# SHDN-CURRENT-S08-V00-5kWDetection.net
KiCad netlist of a schematic drawn in Altium Designer
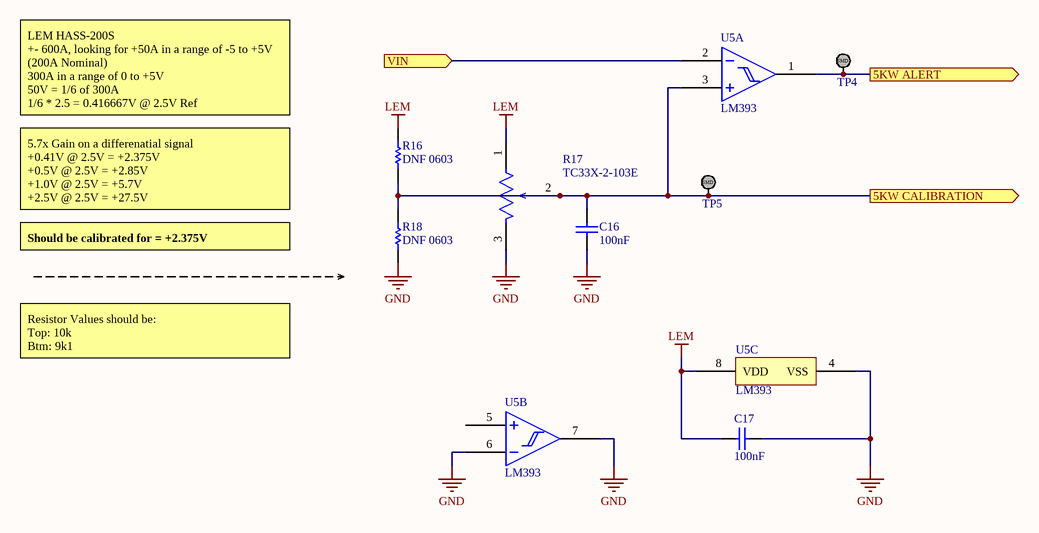
[diagram p0: SHDN-CURRENT-S08-V00-5kWDetection.SchDoc]

(export (version "E")
  (design (tool "Eeschema 10.0.6"))
  (components
    (comp (ref "C16")
      (value "100nF")
      (footprint "Cap_Ceramic_0603")
      (description "Capacitor, Ceramic, SMD, 100nF, 50V, 5%, X7R, 0603")
      (libsource (lib "StandardCapacitors") (part "100nF 50V 5% X7R 0603"))
    )
    (comp (ref "C17")
      (value "100nF")
      (footprint "Cap_Ceramic_0603")
      (description "Capacitor, Ceramic, SMD, 100nF, 50V, 5%, X7R, 0603")
      (libsource (lib "StandardCapacitors") (part "100nF 50V 5% X7R 0603"))
    )
    (comp (ref "R16")
      (value "DNF 0603")
      (footprint "Res_ThinFilm_0603")
      (description "Resistor, SMD, DNF, 0.1W, 0603")
      (libsource (lib "StandardResistors") (part "DNF 0603"))
    )
    (comp (ref "R17")
      (value "TC33X-2-103E")
      (footprint "TC33")
      (description "10 kOhms 0.1W, 1/10W J Lead Surface Mount Trimmer Potentiometer Cermet 1 Turn Top Adjustment")
      (libsource (lib "QUTMS_TrimmerLibrary") (part "TC33X-2-103E"))
    )
    (comp (ref "R18")
      (value "DNF 0603")
      (footprint "Res_ThinFilm_0603")
      (description "Resistor, SMD, DNF, 0.1W, 0603")
      (libsource (lib "StandardResistors") (part "DNF 0603"))
    )
    (comp (ref "TP4")
      (value "TestPoint_SMD")
      (footprint "TestPointSMD")
      (libsource (lib "StandardTest") (part "TestPoint_SMD"))
    )
    (comp (ref "TP5")
      (value "TestPoint_SMD")
      (footprint "TestPointSMD")
      (libsource (lib "StandardTest") (part "TestPoint_SMD"))
    )
    (comp (ref "U5")
      (value "LM393")
      (footprint "TSSOP-8")
      (description "General Purpose Comparitor 2 Circuit 8-SOIC")
      (libsource (lib "") (part "LM393_1"))
    )
  )
  (nets
    (net (code "1") (name "/5KW ALERT") (class "Default")
      (node (ref "TP4") (pin "1") (pinfunction "1_1") (pintype "passive"))
      (node (ref "U5") (pin "1") (pinfunction "OUT1_1") (pintype "passive"))
    )
    (net (code "2") (name "/5KW CALIBRATION") (class "Default")
      (node (ref "C16") (pin "2") (pinfunction "2_2") (pintype "passive"))
      (node (ref "R16") (pin "1") (pinfunction "1_1") (pintype "passive"))
      (node (ref "R17") (pin "2") (pinfunction "2_2") (pintype "passive"))
      (node (ref "R18") (pin "2") (pinfunction "2_2") (pintype "passive"))
      (node (ref "TP5") (pin "1") (pinfunction "1_1") (pintype "passive"))
      (node (ref "U5") (pin "3") (pinfunction "IN1+_3") (pintype "passive"))
    )
    (net (code "3") (name "/VIN") (class "Default")
      (node (ref "U5") (pin "2") (pinfunction "IN1-_2") (pintype "passive"))
    )
    (net (code "4") (name "GND") (class "Default")
      (node (ref "C16") (pin "1") (pinfunction "1_1") (pintype "passive"))
      (node (ref "C17") (pin "2") (pinfunction "2_2") (pintype "passive"))
      (node (ref "R17") (pin "3") (pinfunction "3_3") (pintype "passive"))
      (node (ref "R18") (pin "1") (pinfunction "1_1") (pintype "passive"))
      (node (ref "U5") (pin "4") (pinfunction "VSS_4") (pintype "passive"))
      (node (ref "U5") (pin "6") (pinfunction "IN2-_6") (pintype "passive"))
      (node (ref "U5") (pin "7") (pinfunction "OUT1_7") (pintype "passive"))
    )
    (net (code "5") (name "LEM") (class "Default")
      (node (ref "C17") (pin "1") (pinfunction "1_1") (pintype "passive"))
      (node (ref "R16") (pin "2") (pinfunction "2_2") (pintype "passive"))
      (node (ref "R17") (pin "1") (pinfunction "1_1") (pintype "passive"))
      (node (ref "U5") (pin "8") (pinfunction "VDD_8") (pintype "passive"))
    )
    (net (code "6") (name "unconnected-(U5B-IN2+-Pad5)") (class "Default")
      (node (ref "U5") (pin "5") (pinfunction "IN2+_5") (pintype "passive"))
    )
  )
)
